# Sequencer.net
KiCad netlist of a schematic drawn in EasyEDA Pro
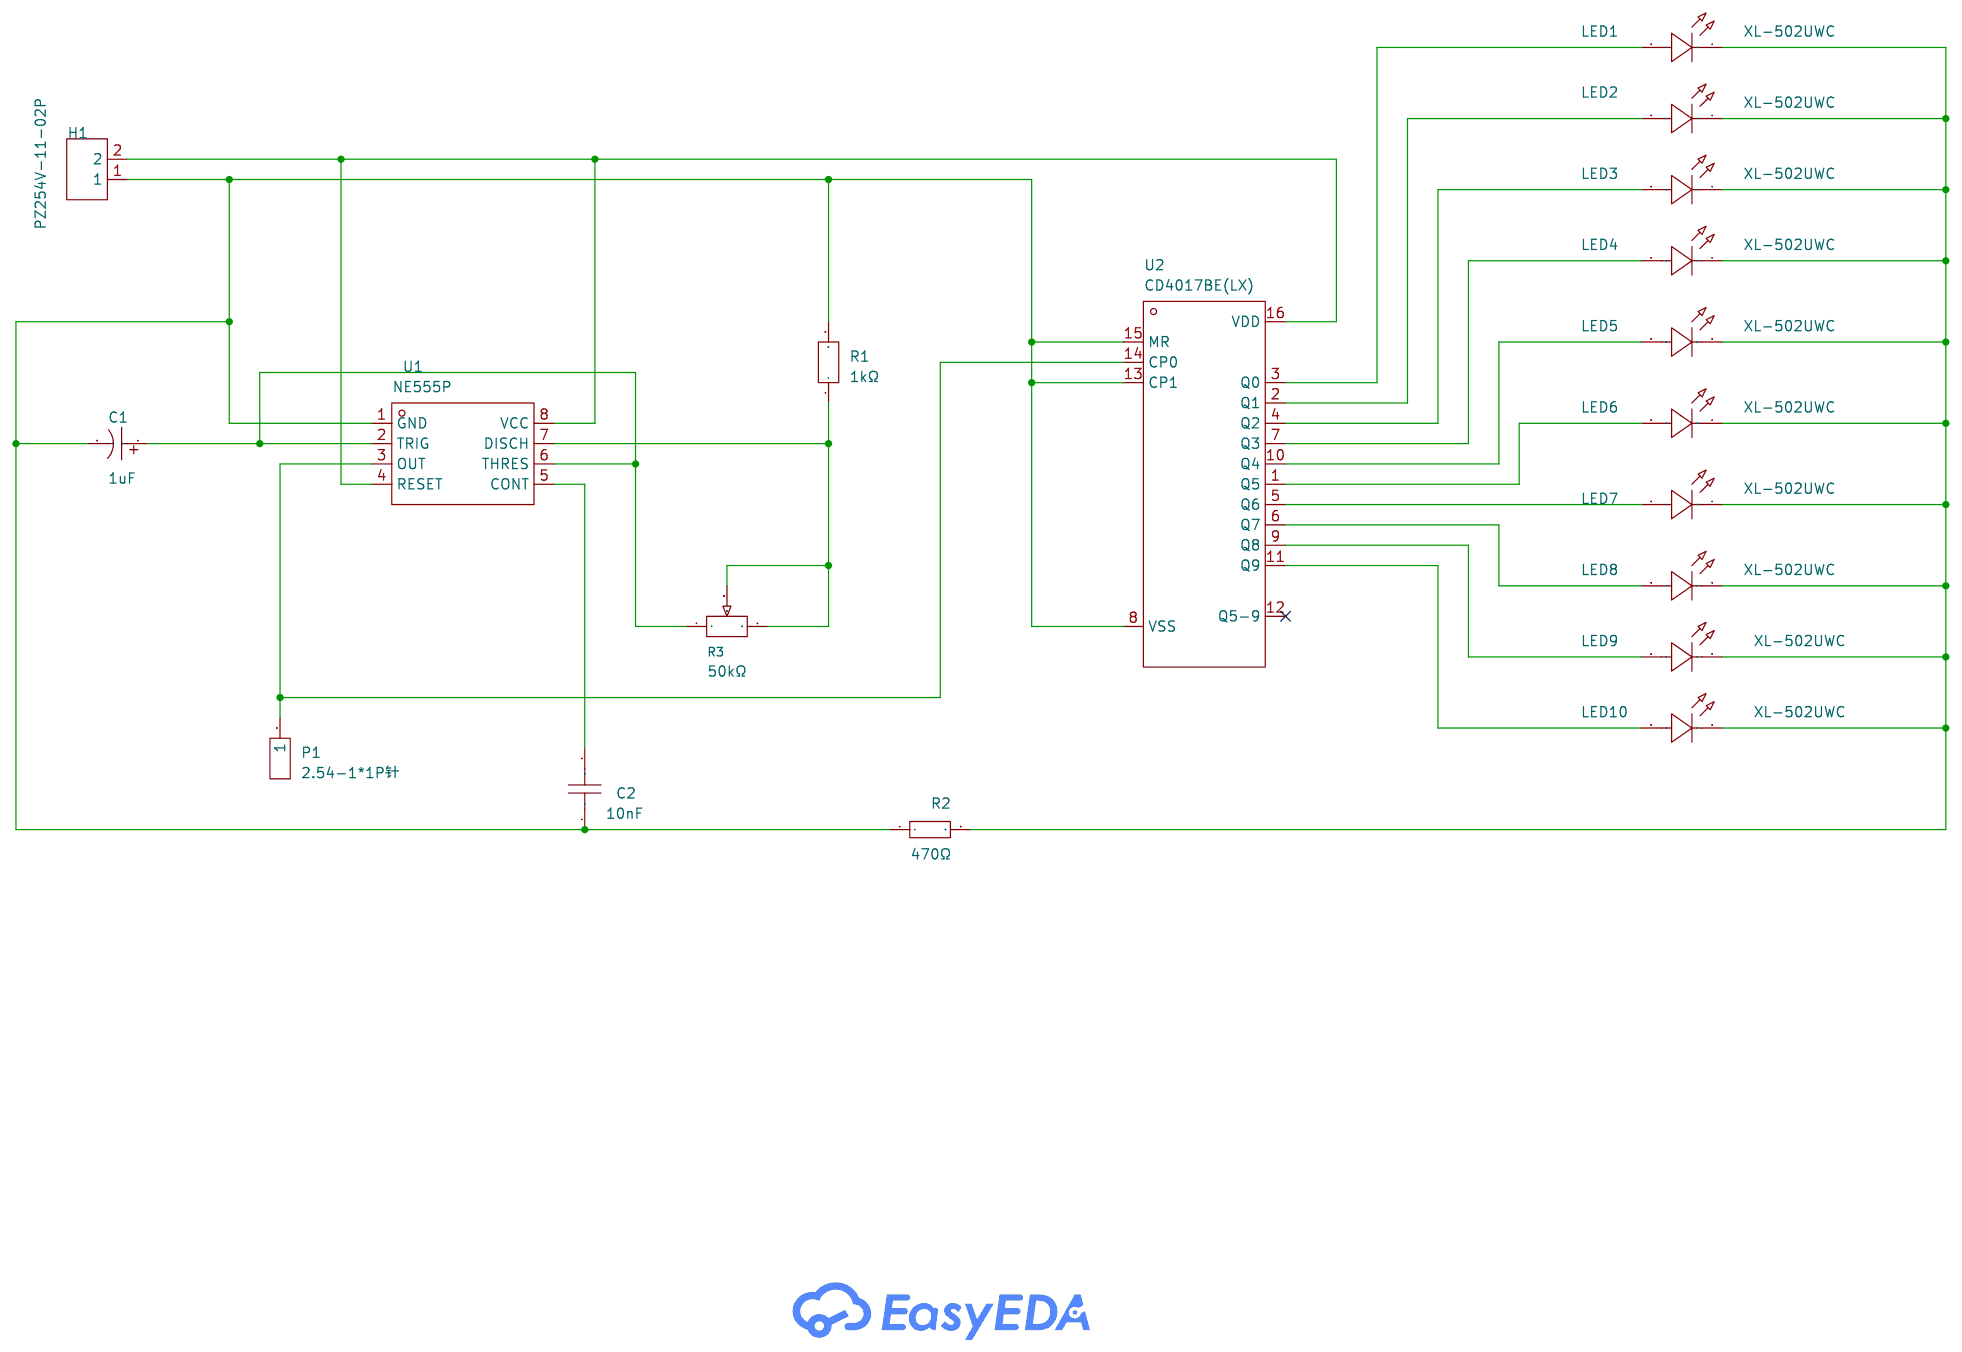
[diagram p0: schematic sheet]

(export (version "E")
  (design (tool "Eeschema 10.0.6"))
  (components
    (comp (ref "C1")
      (value "1uF")
      (footprint "easyedapro:CAP-TH_BD5.0-P2.00-D0.8-FD")
      (fields (field (name "Manufacturer Part") "KF010M050C110A") (field (name "Manufacturer") "CapXon(丰宾)"))
      (libsource (lib "easyedapro") (part "KF010M050C110A"))
    )
    (comp (ref "C2")
      (value "10nF")
      (footprint "easyedapro:CAP-TH_L8.0-W4.0-P5.00-D1.2")
      (fields (field (name "Manufacturer Part") "N09F1B103MN0B0S0N0") (field (name "Manufacturer") "STE(松田)"))
      (libsource (lib "easyedapro") (part "N09F1B103MN0B0S0N0"))
    )
    (comp (ref "H1")
      (value "PZ254V-11-02P")
      (footprint "easyedapro:HDR-TH_2P-P2.54-V-M")
      (fields (field (name "Manufacturer") "XFCN(兴飞)"))
      (libsource (lib "easyedapro") (part "PZ254V-11-02P"))
    )
    (comp (ref "LED1")
      (value "XL-502UWC")
      (footprint "easyedapro:LED-TH_BD5.9-P2.54-RD_WHITE")
      (fields (field (name "Manufacturer") "XINGLIGHT(成兴光)"))
      (libsource (lib "easyedapro") (part "XL-502UWC"))
    )
    (comp (ref "LED2")
      (value "XL-502UWC")
      (footprint "easyedapro:LED-TH_BD5.9-P2.54-RD_WHITE")
      (fields (field (name "Manufacturer") "XINGLIGHT(成兴光)"))
      (libsource (lib "easyedapro") (part "XL-502UWC"))
    )
    (comp (ref "LED3")
      (value "XL-502UWC")
      (footprint "easyedapro:LED-TH_BD5.9-P2.54-RD_WHITE")
      (fields (field (name "Manufacturer") "XINGLIGHT(成兴光)"))
      (libsource (lib "easyedapro") (part "XL-502UWC"))
    )
    (comp (ref "LED4")
      (value "XL-502UWC")
      (footprint "easyedapro:LED-TH_BD5.9-P2.54-RD_WHITE")
      (fields (field (name "Manufacturer") "XINGLIGHT(成兴光)"))
      (libsource (lib "easyedapro") (part "XL-502UWC"))
    )
    (comp (ref "LED5")
      (value "XL-502UWC")
      (footprint "easyedapro:LED-TH_BD5.9-P2.54-RD_WHITE")
      (fields (field (name "Manufacturer") "XINGLIGHT(成兴光)"))
      (libsource (lib "easyedapro") (part "XL-502UWC"))
    )
    (comp (ref "LED6")
      (value "XL-502UWC")
      (footprint "easyedapro:LED-TH_BD5.9-P2.54-RD_WHITE")
      (fields (field (name "Manufacturer") "XINGLIGHT(成兴光)"))
      (libsource (lib "easyedapro") (part "XL-502UWC"))
    )
    (comp (ref "LED7")
      (value "XL-502UWC")
      (footprint "easyedapro:LED-TH_BD5.9-P2.54-RD_WHITE")
      (fields (field (name "Manufacturer") "XINGLIGHT(成兴光)"))
      (libsource (lib "easyedapro") (part "XL-502UWC"))
    )
    (comp (ref "LED8")
      (value "XL-502UWC")
      (footprint "easyedapro:LED-TH_BD5.9-P2.54-RD_WHITE")
      (fields (field (name "Manufacturer") "XINGLIGHT(成兴光)"))
      (libsource (lib "easyedapro") (part "XL-502UWC"))
    )
    (comp (ref "LED9")
      (value "XL-502UWC")
      (footprint "easyedapro:LED-TH_BD5.9-P2.54-RD_WHITE")
      (fields (field (name "Manufacturer") "XINGLIGHT(成兴光)"))
      (libsource (lib "easyedapro") (part "XL-502UWC"))
    )
    (comp (ref "LED10")
      (value "XL-502UWC")
      (footprint "easyedapro:LED-TH_BD5.9-P2.54-RD_WHITE")
      (fields (field (name "Manufacturer") "XINGLIGHT(成兴光)"))
      (libsource (lib "easyedapro") (part "XL-502UWC"))
    )
    (comp (ref "P1")
      (value "2.54-1*1P针")
      (footprint "easyedapro:HDR-TH_1P-P2.54-V-M")
      (fields (field (name "Manufacturer") "BOOMELE(博穆精密)"))
      (libsource (lib "easyedapro") (part "Header-Male-2.54_1x1"))
    )
    (comp (ref "R1")
      (value "1kΩ")
      (footprint "easyedapro:RES-TH_BD2.3-L6.5-P10.50-D0.5")
      (fields (field (name "Manufacturer Part") "MF1/4W-1KΩ±1%T52") (field (name "Manufacturer") "华星机电"))
      (libsource (lib "easyedapro") (part "MF1/4W-1KΩ±1%T52"))
    )
    (comp (ref "R2")
      (value "470Ω")
      (footprint "easyedapro:RES-TH_BD2.2-L6.5-P10.50-D0.6")
      (fields
        (field (name "Manufacturer Part") "MFR0W4F4700A50")
        (field (name "Manufacturer") "UNI-ROYAL(厚声)")
      )
      (libsource (lib "easyedapro") (part "MFR0W4F4700A50"))
    )
    (comp (ref "R3")
      (value "50kΩ")
      (footprint "easyedapro:RES-ADJ-TH_3P-L9.5-W4.85-P2.50-BL-L")
      (fields (field (name "Manufacturer Part") "3296X-1-503") (field (name "Manufacturer") "BOCHEN(博晨)"))
      (libsource (lib "easyedapro") (part "3296X-1-503_C118912"))
    )
    (comp (ref "U1")
      (value "NE555P")
      (footprint "easyedapro:DIP-8_L9.8-W6.6-P2.54-LS7.6-BL")
      (fields (field (name "Manufacturer") "TI(德州仪器)"))
      (libsource (lib "easyedapro") (part "NE555P"))
    )
    (comp (ref "U2")
      (value "CD4017BE(LX)")
      (footprint "easyedapro:PDIP-16_L19.3-W6.4-P2.54-LS7.94-BL")
      (fields (field (name "Manufacturer") "LX(灵星芯微)"))
      (libsource (lib "easyedapro") (part "CD4017BE(LX)"))
    )
  )
  (nets
    (net (code "1") (name "Net-(LED1-A)") (class "Default")
      (node (ref "LED1") (pin "2") (pinfunction "A_2") (pintype "unspecified"))
      (node (ref "U2") (pin "3") (pinfunction "Q0_3") (pintype "unspecified"))
    )
    (net (code "2") (name "Net-(LED1-K)") (class "Default")
      (node (ref "LED1") (pin "1") (pinfunction "K_1") (pintype "unspecified"))
      (node (ref "LED10") (pin "1") (pinfunction "K_1") (pintype "unspecified"))
      (node (ref "LED2") (pin "1") (pinfunction "K_1") (pintype "unspecified"))
      (node (ref "LED3") (pin "1") (pinfunction "K_1") (pintype "unspecified"))
      (node (ref "LED4") (pin "1") (pinfunction "K_1") (pintype "unspecified"))
      (node (ref "LED5") (pin "1") (pinfunction "K_1") (pintype "unspecified"))
      (node (ref "LED6") (pin "1") (pinfunction "K_1") (pintype "unspecified"))
      (node (ref "LED7") (pin "1") (pinfunction "K_1") (pintype "unspecified"))
      (node (ref "LED8") (pin "1") (pinfunction "K_1") (pintype "unspecified"))
      (node (ref "LED9") (pin "1") (pinfunction "K_1") (pintype "unspecified"))
      (node (ref "R2") (pin "2") (pinfunction "2_2") (pintype "input"))
    )
    (net (code "3") (name "Net-(LED2-A)") (class "Default")
      (node (ref "LED2") (pin "2") (pinfunction "A_2") (pintype "unspecified"))
      (node (ref "U2") (pin "2") (pinfunction "Q1_2") (pintype "unspecified"))
    )
    (net (code "4") (name "Net-(LED3-A)") (class "Default")
      (node (ref "LED3") (pin "2") (pinfunction "A_2") (pintype "unspecified"))
      (node (ref "U2") (pin "4") (pinfunction "Q2_4") (pintype "unspecified"))
    )
    (net (code "5") (name "Net-(LED4-A)") (class "Default")
      (node (ref "LED4") (pin "2") (pinfunction "A_2") (pintype "unspecified"))
      (node (ref "U2") (pin "7") (pinfunction "Q3_7") (pintype "unspecified"))
    )
    (net (code "6") (name "Net-(LED5-A)") (class "Default")
      (node (ref "LED5") (pin "2") (pinfunction "A_2") (pintype "unspecified"))
      (node (ref "U2") (pin "10") (pinfunction "Q4_10") (pintype "unspecified"))
    )
    (net (code "7") (name "Net-(LED6-A)") (class "Default")
      (node (ref "LED6") (pin "2") (pinfunction "A_2") (pintype "unspecified"))
      (node (ref "U2") (pin "1") (pinfunction "Q5_1") (pintype "unspecified"))
    )
    (net (code "8") (name "Net-(LED7-A)") (class "Default")
      (node (ref "LED7") (pin "2") (pinfunction "A_2") (pintype "unspecified"))
      (node (ref "U2") (pin "5") (pinfunction "Q6_5") (pintype "unspecified"))
    )
    (net (code "9") (name "Net-(LED8-A)") (class "Default")
      (node (ref "LED8") (pin "2") (pinfunction "A_2") (pintype "unspecified"))
      (node (ref "U2") (pin "6") (pinfunction "Q7_6") (pintype "unspecified"))
    )
    (net (code "10") (name "Net-(LED9-A)") (class "Default")
      (node (ref "LED9") (pin "2") (pinfunction "A_2") (pintype "unspecified"))
      (node (ref "U2") (pin "9") (pinfunction "Q8_9") (pintype "unspecified"))
    )
    (net (code "11") (name "Net-(LED10-A)") (class "Default")
      (node (ref "LED10") (pin "2") (pinfunction "A_2") (pintype "unspecified"))
      (node (ref "U2") (pin "11") (pinfunction "Q9_11") (pintype "unspecified"))
    )
    (net (code "12") (name "Net-(U1-CONT)") (class "Default")
      (node (ref "C2") (pin "2") (pinfunction "2_2") (pintype "unspecified"))
      (node (ref "U1") (pin "5") (pinfunction "CONT_5") (pintype "input"))
    )
    (net (code "13") (name "Net-(U1-DISCH)") (class "Default")
      (node (ref "R1") (pin "1") (pinfunction "1_1") (pintype "unspecified"))
      (node (ref "R3") (pin "2") (pinfunction "2_2") (pintype "input"))
      (node (ref "R3") (pin "3") (pinfunction "3_3") (pintype "input"))
      (node (ref "U1") (pin "7") (pinfunction "DISCH_7") (pintype "input"))
    )
    (net (code "14") (name "Net-(U1-GND)") (class "Default")
      (node (ref "C1") (pin "2") (pinfunction "2_2") (pintype "input"))
      (node (ref "C2") (pin "1") (pinfunction "1_1") (pintype "unspecified"))
      (node (ref "H1") (pin "1") (pinfunction "1_1") (pintype "unspecified"))
      (node (ref "R1") (pin "2") (pinfunction "2_2") (pintype "unspecified"))
      (node (ref "R2") (pin "1") (pinfunction "1_1") (pintype "input"))
      (node (ref "U1") (pin "1") (pinfunction "GND_1") (pintype "input"))
      (node (ref "U2") (pin "13") (pinfunction "CP1_13") (pintype "unspecified"))
      (node (ref "U2") (pin "15") (pinfunction "MR_15") (pintype "unspecified"))
      (node (ref "U2") (pin "8") (pinfunction "VSS_8") (pintype "unspecified"))
    )
    (net (code "15") (name "Net-(U1-OUT)") (class "Default")
      (node (ref "P1") (pin "1") (pinfunction "1_1") (pintype "input"))
      (node (ref "U1") (pin "3") (pinfunction "OUT_3") (pintype "input"))
      (node (ref "U2") (pin "14") (pinfunction "CP0_14") (pintype "unspecified"))
    )
    (net (code "16") (name "Net-(U1-RESET)") (class "Default")
      (node (ref "H1") (pin "2") (pinfunction "2_2") (pintype "unspecified"))
      (node (ref "U1") (pin "4") (pinfunction "RESET_4") (pintype "input"))
      (node (ref "U1") (pin "8") (pinfunction "VCC_8") (pintype "input"))
      (node (ref "U2") (pin "16") (pinfunction "VDD_16") (pintype "unspecified"))
    )
    (net (code "17") (name "Net-(U1-THRES)") (class "Default")
      (node (ref "C1") (pin "1") (pinfunction "1_1") (pintype "input"))
      (node (ref "R3") (pin "1") (pinfunction "1_1") (pintype "input"))
      (node (ref "U1") (pin "2") (pinfunction "TRIG_2") (pintype "input"))
      (node (ref "U1") (pin "6") (pinfunction "THRES_6") (pintype "input"))
    )
    (net (code "18") (name "unconnected-(U2-Q5-9-Pad12)") (class "Default")
      (node (ref "U2") (pin "12") (pinfunction "Q5-9_12") (pintype "unspecified+no_connect"))
    )
  )
)
